# sierpinski-tree_2020-12-05_14-07-16.net
KiCad netlist of a schematic drawn in EasyEDA
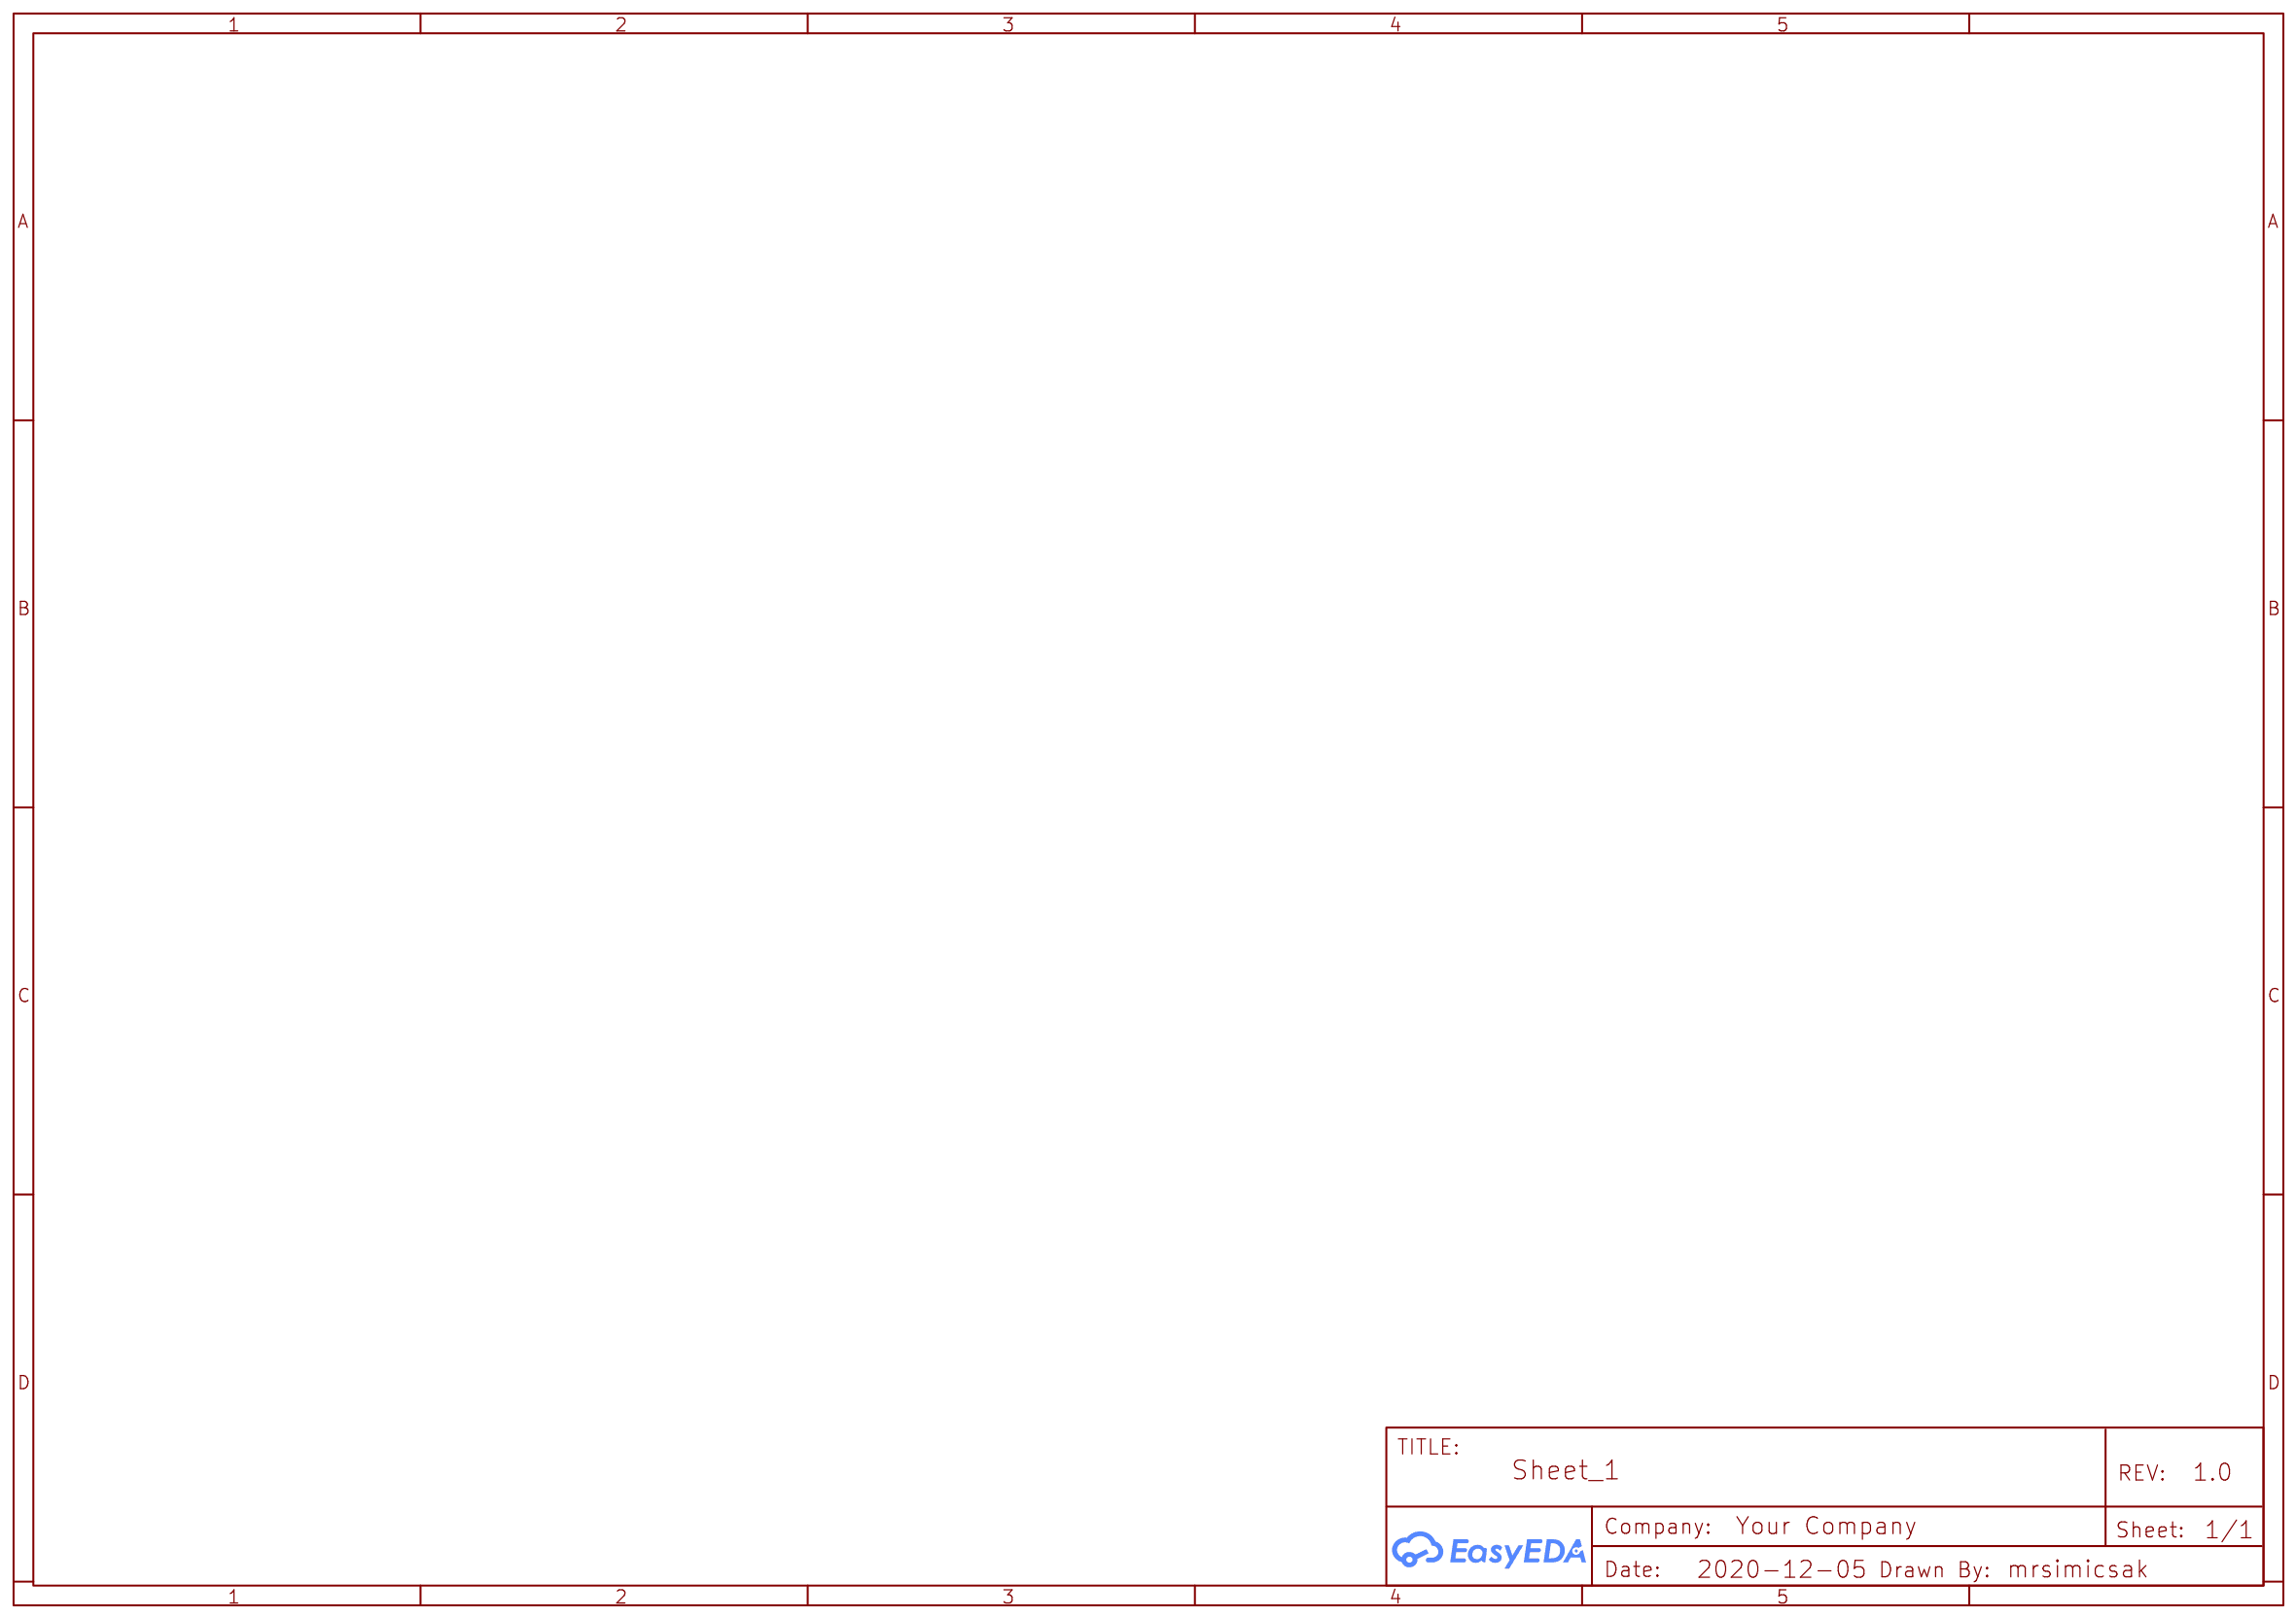
[diagram p0: Sheet_1]
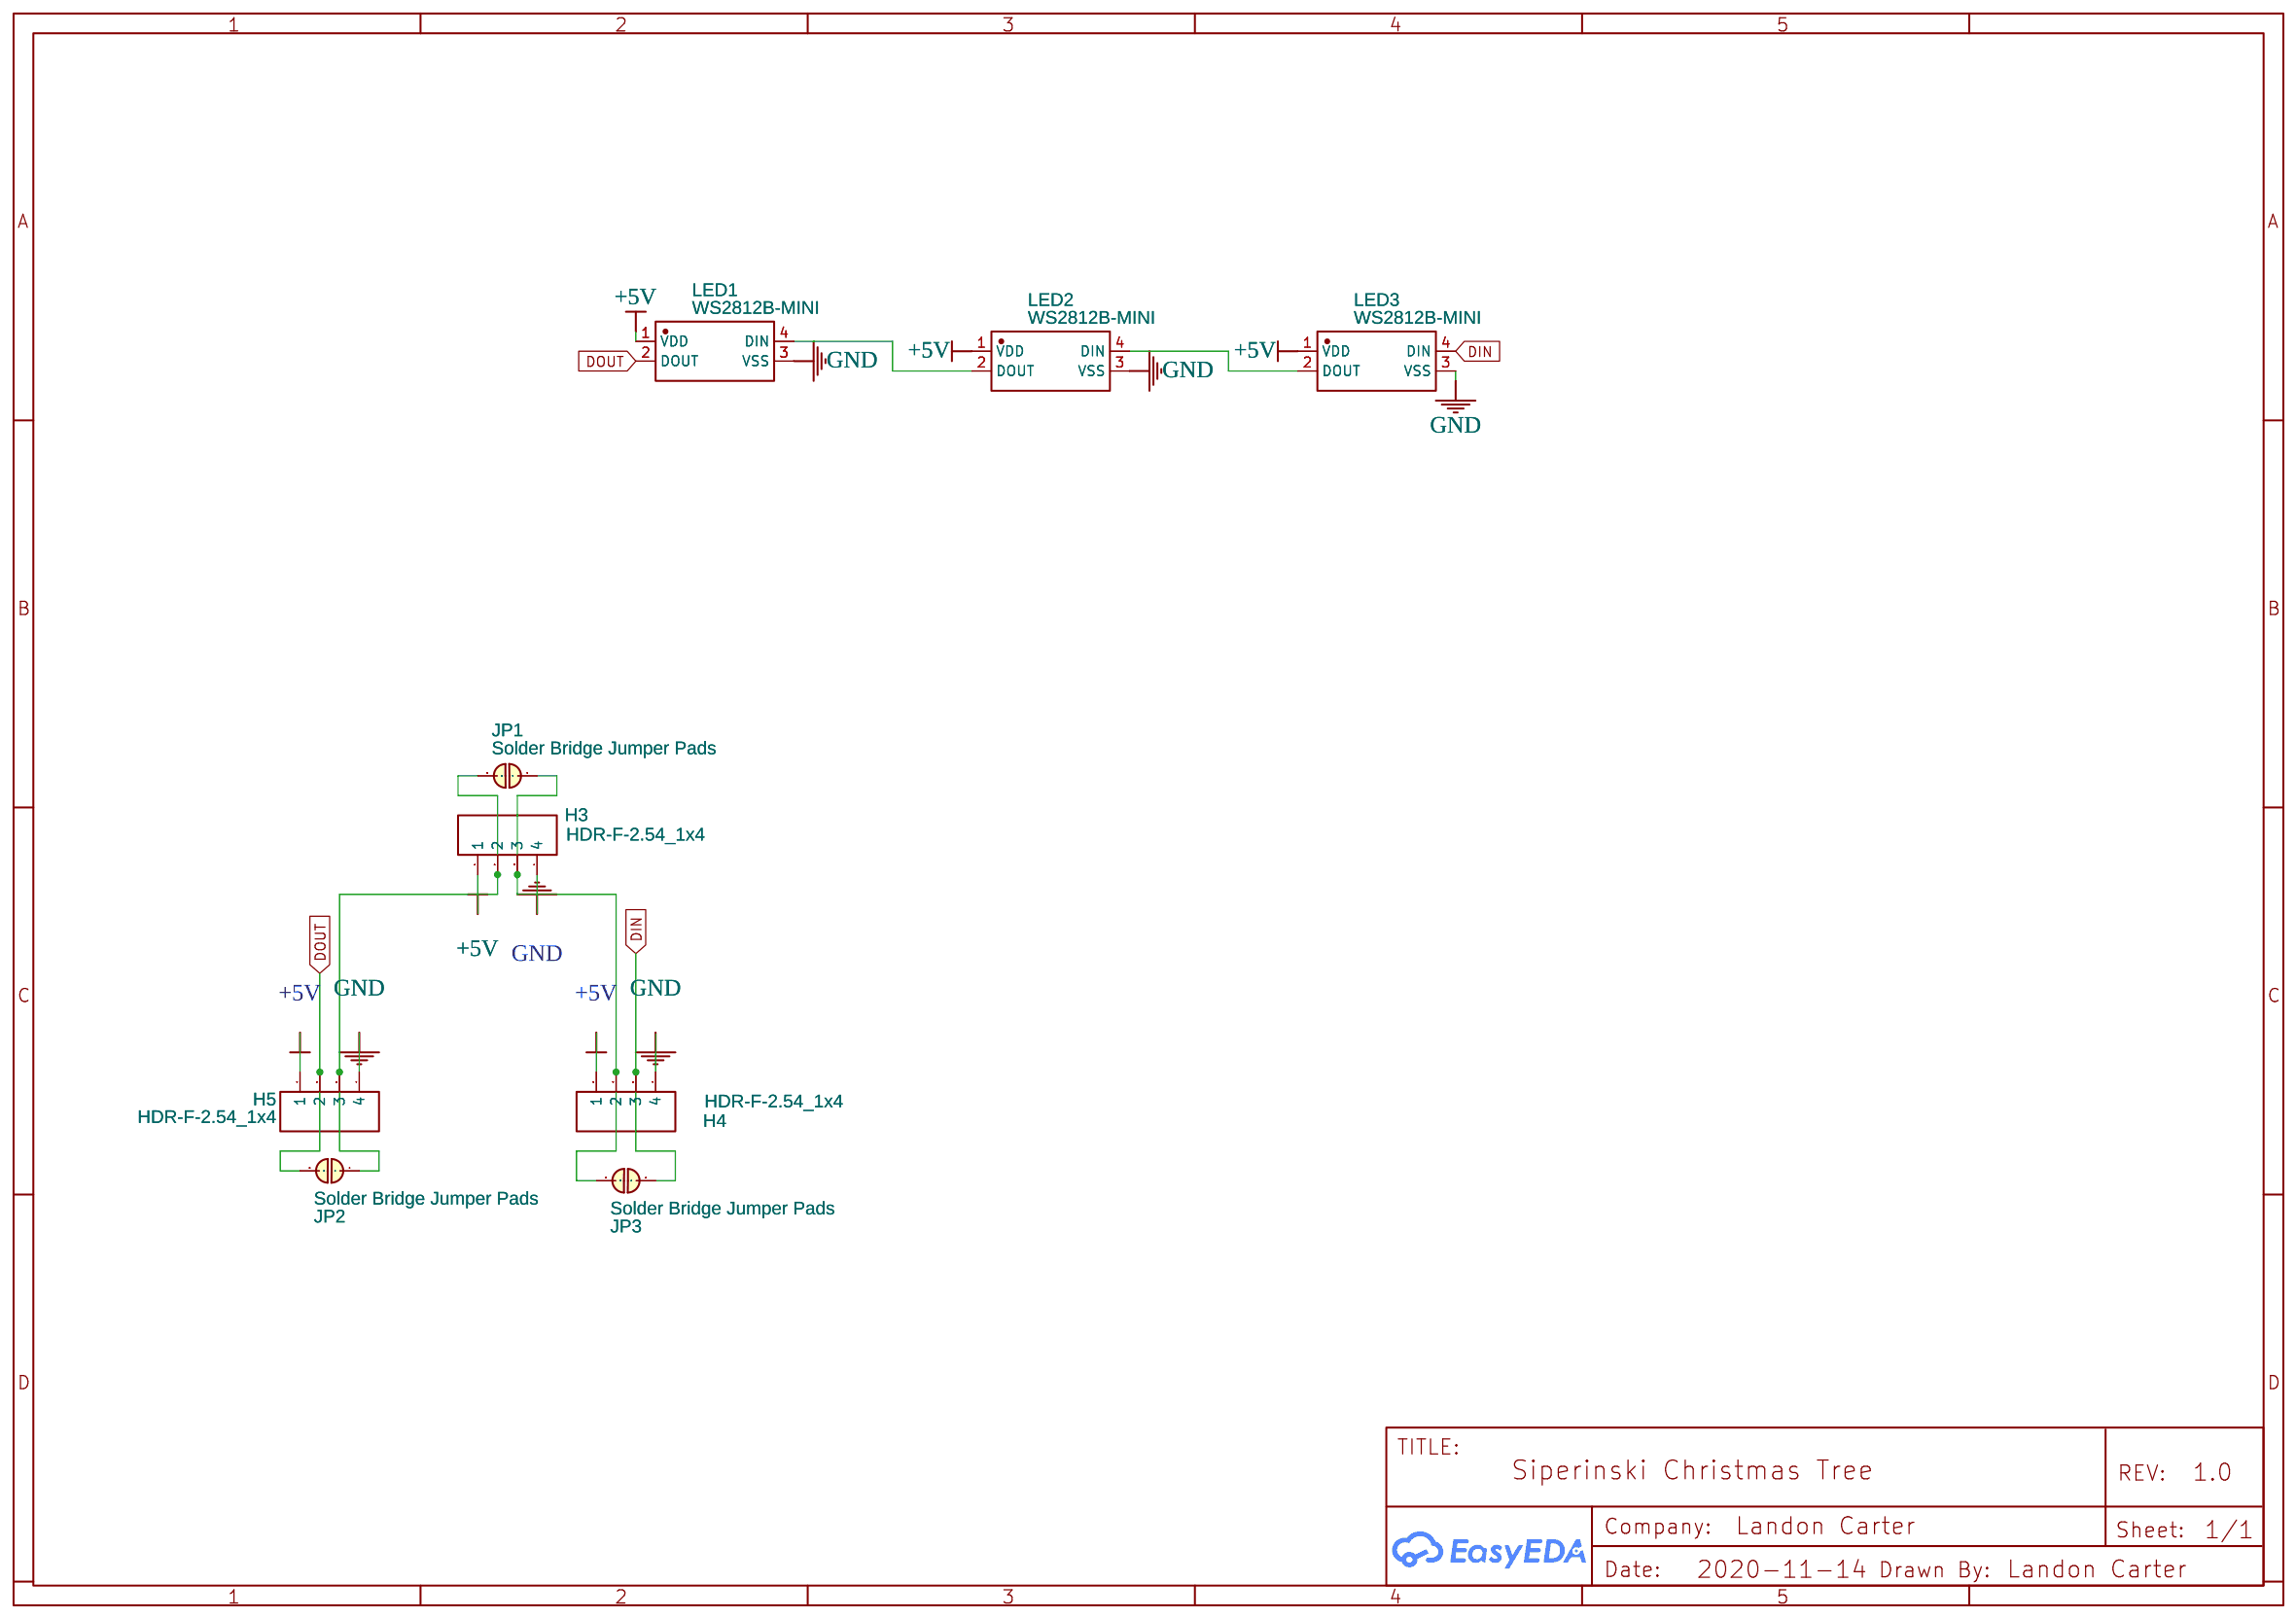
[diagram p1: Sheet_1#2]

(export (version "E")
  (design (tool "Eeschema 10.0.6"))
  (components
    (comp (ref "H3")
      (value "HDR-F-2.54_1x4")
      (fields (field (name "BOM_Supplier Part") "C225501"))
      (libsource (lib "") (part "HDR-F-2.54_1x4_1"))
    )
    (comp (ref "H4")
      (value "HDR-F-2.54_1x4")
      (fields (field (name "BOM_Supplier Part") "C225501"))
      (libsource (lib "") (part "HDR-F-2.54_1x4"))
    )
    (comp (ref "H5")
      (value "HDR-F-2.54_1x4")
      (fields (field (name "BOM_Supplier Part") "C225501"))
      (libsource (lib "") (part "HDR-F-2.54_1x4"))
    )
    (comp (ref "JP1")
      (value "Solder Bridge Jumper Pads")
      (libsource (lib "") (part "Solder Bridge Jumper Pads_1"))
    )
    (comp (ref "JP2")
      (value "Solder Bridge Jumper Pads")
      (libsource (lib "") (part "Solder Bridge Jumper Pads"))
    )
    (comp (ref "JP3")
      (value "Solder Bridge Jumper Pads")
      (libsource (lib "") (part "Solder Bridge Jumper Pads"))
    )
    (comp (ref "LED1")
      (value "WS2812B-MINI")
      (fields
        (field (name "BOM_Manufacturer Part") "WS2812B-Mini")
        (field (name "BOM_Supplier Part") "C527089")
      )
      (libsource (lib "") (part "WS2812B-MINI"))
    )
    (comp (ref "LED2")
      (value "WS2812B-MINI")
      (fields
        (field (name "BOM_Manufacturer Part") "WS2812B-Mini")
        (field (name "BOM_Supplier Part") "C527089")
      )
      (libsource (lib "") (part "WS2812B-MINI"))
    )
    (comp (ref "LED3")
      (value "WS2812B-MINI")
      (fields
        (field (name "BOM_Manufacturer Part") "WS2812B-Mini")
        (field (name "BOM_Supplier Part") "C527089")
      )
      (libsource (lib "") (part "WS2812B-MINI"))
    )
  )
  (nets
    (net (code "1") (name "+5V") (class "Default")
      (node (ref "H3") (pin "1") (pinfunction "1_1") (pintype "unspecified"))
      (node (ref "H4") (pin "1") (pinfunction "1_1") (pintype "unspecified"))
      (node (ref "H5") (pin "1") (pinfunction "1_1") (pintype "unspecified"))
      (node (ref "LED1") (pin "1") (pinfunction "VDD_1") (pintype "unspecified"))
      (node (ref "LED2") (pin "1") (pinfunction "VDD_1") (pintype "unspecified"))
      (node (ref "LED3") (pin "1") (pinfunction "VDD_1") (pintype "unspecified"))
    )
    (net (code "2") (name "DIN") (class "Default")
      (node (ref "H4") (pin "3") (pinfunction "3_3") (pintype "unspecified"))
      (node (ref "JP3") (pin "1") (pinfunction "1_1") (pintype "bidirectional"))
      (node (ref "LED3") (pin "4") (pinfunction "DIN_4") (pintype "unspecified"))
    )
    (net (code "3") (name "DOUT") (class "Default")
      (node (ref "H5") (pin "2") (pinfunction "2_2") (pintype "unspecified"))
      (node (ref "JP2") (pin "2") (pinfunction "2_2") (pintype "bidirectional"))
      (node (ref "LED1") (pin "2") (pinfunction "DOUT_2") (pintype "unspecified"))
    )
    (net (code "4") (name "GND") (class "Default")
      (node (ref "H3") (pin "4") (pinfunction "4_4") (pintype "unspecified"))
      (node (ref "H4") (pin "4") (pinfunction "4_4") (pintype "unspecified"))
      (node (ref "H5") (pin "4") (pinfunction "4_4") (pintype "unspecified"))
      (node (ref "LED1") (pin "3") (pinfunction "VSS_3") (pintype "unspecified"))
      (node (ref "LED2") (pin "3") (pinfunction "VSS_3") (pintype "unspecified"))
      (node (ref "LED3") (pin "3") (pinfunction "VSS_3") (pintype "unspecified"))
    )
    (net (code "5") (name "Net-(H3-Pad2)") (class "Default")
      (node (ref "H3") (pin "2") (pinfunction "2_2") (pintype "unspecified"))
      (node (ref "H5") (pin "3") (pinfunction "3_3") (pintype "unspecified"))
      (node (ref "JP1") (pin "2") (pinfunction "2_2") (pintype "bidirectional"))
      (node (ref "JP2") (pin "1") (pinfunction "1_1") (pintype "bidirectional"))
    )
    (net (code "6") (name "Net-(H3-Pad3)") (class "Default")
      (node (ref "H3") (pin "3") (pinfunction "3_3") (pintype "unspecified"))
      (node (ref "H4") (pin "2") (pinfunction "2_2") (pintype "unspecified"))
      (node (ref "JP1") (pin "1") (pinfunction "1_1") (pintype "bidirectional"))
      (node (ref "JP3") (pin "2") (pinfunction "2_2") (pintype "bidirectional"))
    )
    (net (code "7") (name "Net-(LED1-DIN)") (class "Default")
      (node (ref "LED1") (pin "4") (pinfunction "DIN_4") (pintype "unspecified"))
      (node (ref "LED2") (pin "2") (pinfunction "DOUT_2") (pintype "unspecified"))
    )
    (net (code "8") (name "Net-(LED2-DIN)") (class "Default")
      (node (ref "LED2") (pin "4") (pinfunction "DIN_4") (pintype "unspecified"))
      (node (ref "LED3") (pin "2") (pinfunction "DOUT_2") (pintype "unspecified"))
    )
  )
)
